# Lora-Breakout.net
KiCad netlist of a schematic drawn in EAGLE
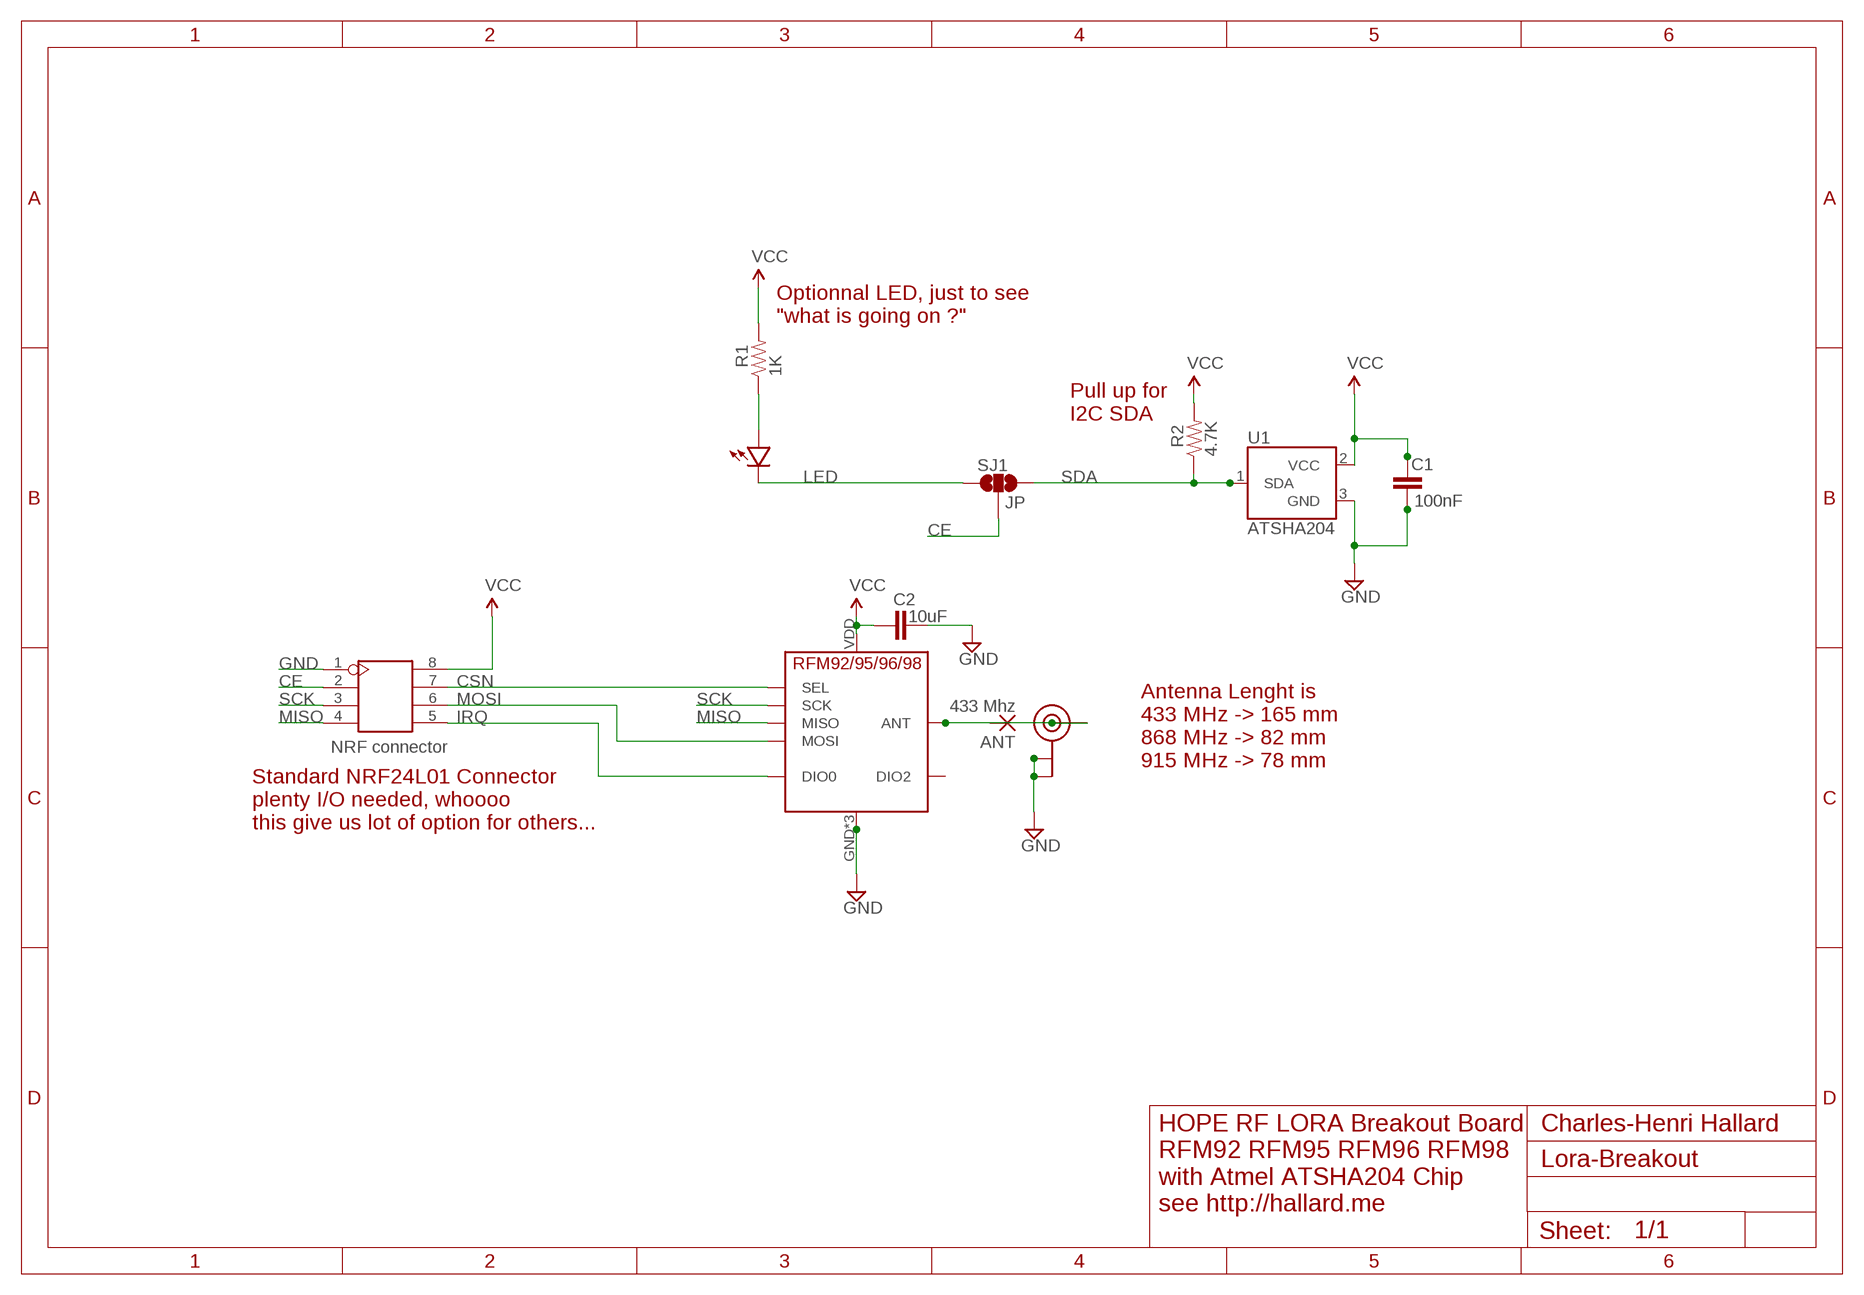
[diagram p0: schematic, sheet 1]

(export (version "E")
  (design (tool "Eeschema 10.0.6"))
  (components
    (comp (ref "ANT")
      (value "433 Mhz")
      (footprint "eagle-import:1,6_0,8")
      (libsource (lib "eagle-import") (part "1,6/0,8"))
    )
    (comp (ref "C1")
      (value "100nF")
      (footprint "eagle-import:0805-CAP")
      (libsource (lib "eagle-import") (part "CAP0805-CAP"))
    )
    (comp (ref "C2")
      (value "10uF")
      (footprint "eagle-import:0805-CAP")
      (libsource (lib "eagle-import") (part "CAP0805-CAP"))
    )
    (comp (ref "J1")
      (value "NRF connector")
      (footprint "eagle-import:2X4P-2.54")
      (libsource (lib "eagle-import") (part "HEADER-2X4P-2.54"))
    )
    (comp (ref "R1")
      (value "1K")
      (footprint "eagle-import:0805-RES")
      (libsource (lib "eagle-import") (part "RESISTOR0805-RES"))
    )
    (comp (ref "R2")
      (value "4.7K")
      (footprint "eagle-import:0805-RES")
      (libsource (lib "eagle-import") (part "RESISTOR0805-RES"))
    )
    (comp (ref "SJ1")
      (value "JP")
      (footprint "eagle-import:PAD-JUMPER-3-NO_YES_SILK")
      (libsource (lib "eagle-import") (part "JUMPER-PAD-3-NOYES_SILK"))
    )
    (comp (ref "U$1")
      (value "LED0805-LARGE")
      (footprint "eagle-import:0805-LED-LARGEPADS")
      (libsource (lib "eagle-import") (part "LED0805-LARGE"))
    )
    (comp (ref "U$3")
      (value "RFM95")
      (footprint "eagle-import:RFM95")
      (libsource (lib "eagle-import") (part "RFM95"))
    )
    (comp (ref "U-FL")
      (value "U.FL")
      (footprint "eagle-import:U.FL")
      (libsource (lib "eagle-import") (part "U.FL"))
    )
    (comp (ref "U1")
      (value "ATSHA204")
      (footprint "eagle-import:SOT23-3")
      (libsource (lib "eagle-import") (part "ATSHA204-TSU"))
    )
  )
  (nets
    (net (code "1") (name "/CE") (class "Default")
      (node (ref "J1") (pin "2") (pinfunction "2_2") (pintype "bidirectional"))
      (node (ref "SJ1") (pin "2") (pinfunction "2_2") (pintype "passive"))
    )
    (net (code "2") (name "/CSN") (class "Default")
      (node (ref "J1") (pin "7") (pinfunction "7_7") (pintype "bidirectional"))
      (node (ref "U$3") (pin "NSS") (pinfunction "SEL_NSS") (pintype "input"))
    )
    (net (code "3") (name "/IRQ") (class "Default")
      (node (ref "J1") (pin "5") (pinfunction "5_5") (pintype "bidirectional"))
      (node (ref "U$3") (pin "DIO0") (pinfunction "DIO0_DIO0") (pintype "open_collector"))
    )
    (net (code "4") (name "/LED") (class "Default")
      (node (ref "SJ1") (pin "1") (pinfunction "1_1") (pintype "passive"))
      (node (ref "U$1") (pin "MINUS") (pinfunction "MINUS_MINUS") (pintype "passive"))
    )
    (net (code "5") (name "/MISO") (class "Default")
      (node (ref "J1") (pin "4") (pinfunction "4_4") (pintype "bidirectional"))
      (node (ref "U$3") (pin "MISO") (pinfunction "MISO_MISO") (pintype "input"))
    )
    (net (code "6") (name "/MOSI") (class "Default")
      (node (ref "J1") (pin "6") (pinfunction "6_6") (pintype "bidirectional"))
      (node (ref "U$3") (pin "MOSI") (pinfunction "MOSI_MOSI") (pintype "output"))
    )
    (net (code "7") (name "/SCK") (class "Default")
      (node (ref "J1") (pin "3") (pinfunction "3_3") (pintype "bidirectional"))
      (node (ref "U$3") (pin "SCK") (pinfunction "SCK_SCK") (pintype "input"))
    )
    (net (code "8") (name "/SDA") (class "Default")
      (node (ref "R2") (pin "1") (pinfunction "1_1") (pintype "passive"))
      (node (ref "SJ1") (pin "3") (pinfunction "3_3") (pintype "passive"))
      (node (ref "U1") (pin "1") (pinfunction "SDA_1") (pintype "bidirectional"))
    )
    (net (code "9") (name "GND") (class "Default")
      (node (ref "C1") (pin "2") (pinfunction "2_2") (pintype "passive"))
      (node (ref "C2") (pin "2") (pinfunction "2_2") (pintype "passive"))
      (node (ref "J1") (pin "1") (pinfunction "1_1") (pintype "bidirectional"))
      (node (ref "U$3") (pin "GND") (pinfunction "GND_GND") (pintype "power_in"))
      (node (ref "U$3") (pin "GND1") (pinfunction "GND_GND1") (pintype "power_in"))
      (node (ref "U$3") (pin "GND2") (pinfunction "GND_GND2") (pintype "power_in"))
      (node (ref "U-FL") (pin "1") (pinfunction "GND_1") (pintype "passive"))
      (node (ref "U-FL") (pin "2") (pinfunction "GND_2") (pintype "passive"))
      (node (ref "U1") (pin "3") (pinfunction "GND_3") (pintype "bidirectional"))
    )
    (net (code "10") (name "Net-(ANT-P)") (class "Default")
      (node (ref "ANT") (pin "1") (pinfunction "P_1") (pintype "passive"))
      (node (ref "U$3") (pin "ANT") (pinfunction "ANT_ANT") (pintype "passive"))
      (node (ref "U-FL") (pin "3") (pinfunction "SIGNAL_3") (pintype "passive"))
    )
    (net (code "11") (name "Net-(R1-Pad1)") (class "Default")
      (node (ref "R1") (pin "1") (pinfunction "1_1") (pintype "passive"))
      (node (ref "U$1") (pin "PLUS") (pinfunction "PLUS_PLUS") (pintype "passive"))
    )
    (net (code "12") (name "VCC") (class "Default")
      (node (ref "C1") (pin "1") (pinfunction "1_1") (pintype "passive"))
      (node (ref "C2") (pin "1") (pinfunction "1_1") (pintype "passive"))
      (node (ref "J1") (pin "8") (pinfunction "8_8") (pintype "bidirectional"))
      (node (ref "R1") (pin "2") (pinfunction "2_2") (pintype "passive"))
      (node (ref "R2") (pin "2") (pinfunction "2_2") (pintype "passive"))
      (node (ref "U$3") (pin "VDD") (pinfunction "VCC_VDD") (pintype "power_in"))
      (node (ref "U1") (pin "2") (pinfunction "VCC_2") (pintype "bidirectional"))
    )
    (net (code "13") (name "unconnected-(U$3-PadDIO2)") (class "Default")
      (node (ref "U$3") (pin "DIO2") (pinfunction "DIO2_DIO2") (pintype "open_collector"))
    )
  )
)
